# 3-3.net
KiCad netlist of a schematic drawn in Altium Designer
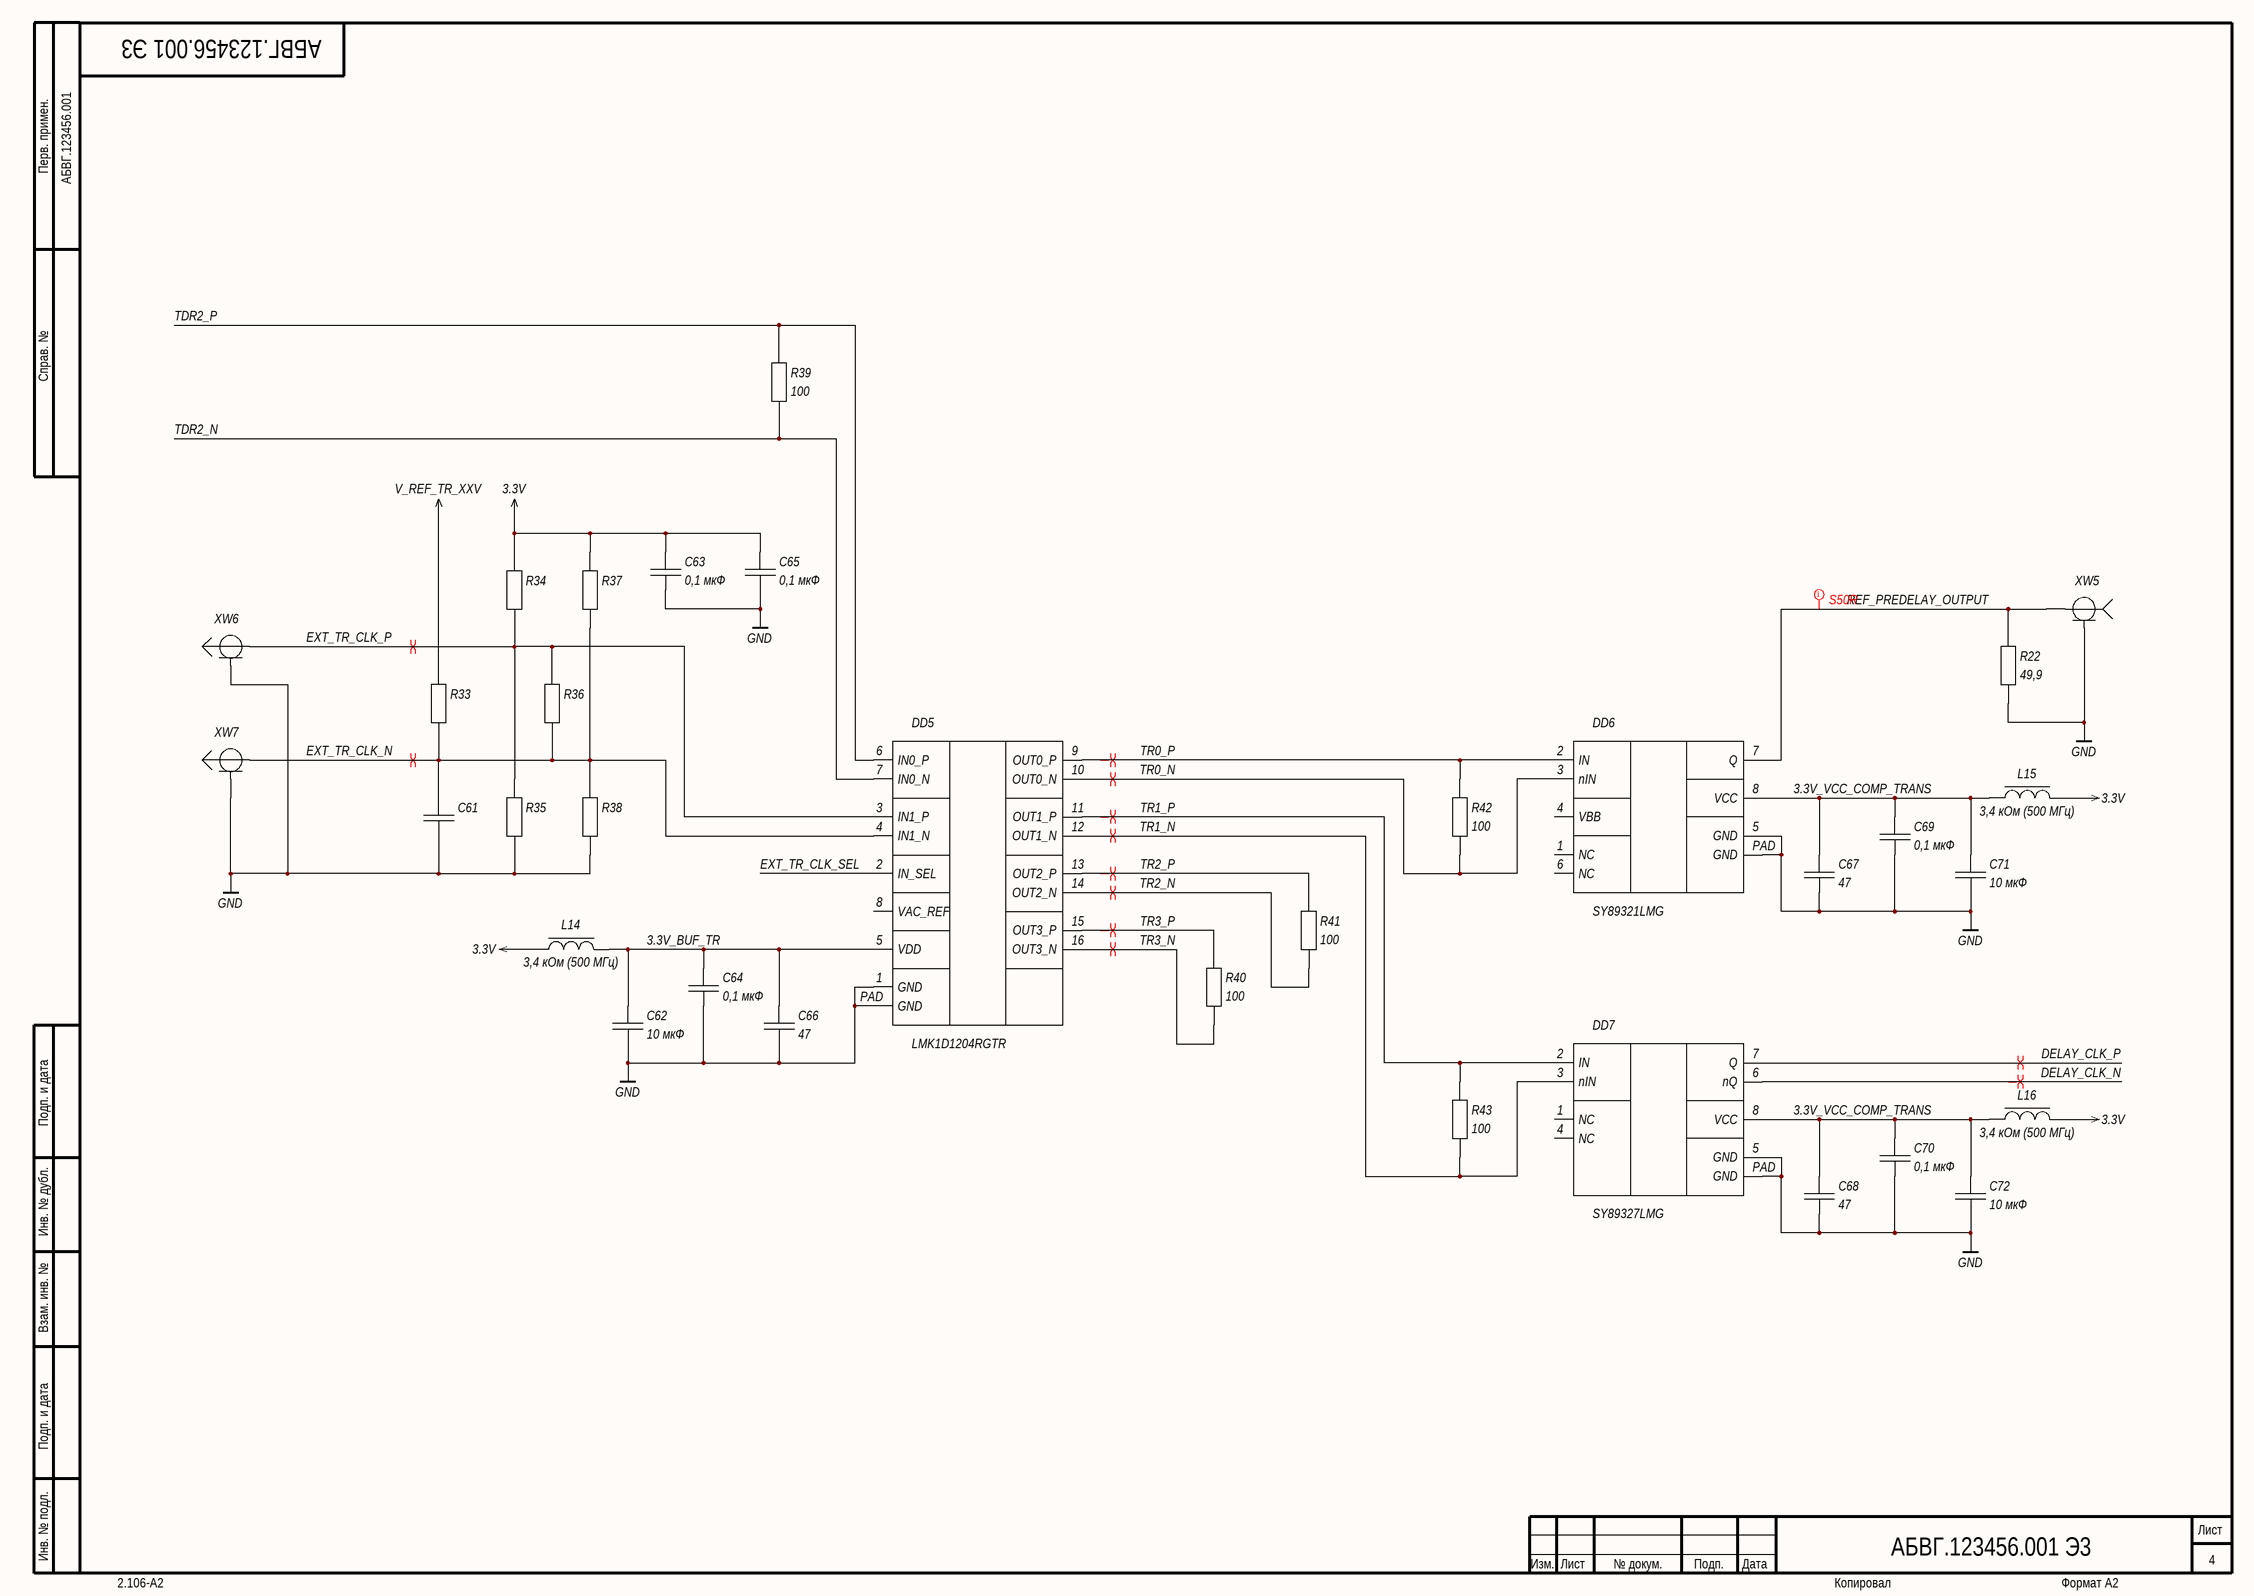
[diagram p0: Э3-3 Внешний триггер.SchDoc]

(export (version "E")
  (design (tool "Eeschema 10.0.6"))
  (components
    (comp (ref "C61")
      (value "~")
      (footprint "C0402-B-0.5mm")
      (fields (field (name "PARTNUMBER") "GRM155R71H104KE14D"))
      (libsource (lib "Capacitors") (part "Non Polar Ver."))
    )
    (comp (ref "C62")
      (value "10 мкФ")
      (footprint "C0603-B-0.8mm")
      (description "0603 X5R 10 мкФ ±20 % 25 В")
      (fields (field (name "PARTNUMBER") "GRM188R61E106MA73"))
      (libsource (lib "Capacitors") (part "Non Polar Ver."))
    )
    (comp (ref "C63")
      (value "0,1 мкФ")
      (footprint "C0402-B-0.5mm")
      (description "0402 X7R 0,1 мкФ ±10 % 50 В")
      (fields (field (name "PARTNUMBER") "GRM155R71H104KE14D"))
      (libsource (lib "Capacitors") (part "Non Polar Ver."))
    )
    (comp (ref "C64")
      (value "0,1 мкФ")
      (footprint "C0402-B-0.5mm")
      (description "0402 X7R 0,1 мкФ ±10 % 50 В")
      (fields (field (name "PARTNUMBER") "GRM155R71H104KE14D"))
      (libsource (lib "Capacitors") (part "Non Polar Ver."))
    )
    (comp (ref "C65")
      (value "0,1 мкФ")
      (footprint "C0402-B-0.5mm")
      (description "0402 X7R 0,1 мкФ ±10 % 50 В")
      (fields (field (name "PARTNUMBER") "GRM155R71H104KE14D"))
      (libsource (lib "Capacitors") (part "Non Polar Ver."))
    )
    (comp (ref "C66")
      (value "47")
      (footprint "C0402-B-0.5mm")
      (description "0402 NP0 47 пФ ±5 % 50 В")
      (fields (field (name "PARTNUMBER") "GCM1555C1H470JA16"))
      (libsource (lib "Capacitors") (part "Non Polar Ver."))
    )
    (comp (ref "C67")
      (value "47")
      (footprint "C0402-B-0.5mm")
      (description "0402 NP0 47 пФ ±5 % 50 В")
      (fields (field (name "PARTNUMBER") "GCM1555C1H470JA16"))
      (libsource (lib "Capacitors") (part "Non Polar Ver."))
    )
    (comp (ref "C68")
      (value "47")
      (footprint "C0402-B-0.5mm")
      (description "0402 NP0 47 пФ ±5 % 50 В")
      (fields (field (name "PARTNUMBER") "GCM1555C1H470JA16"))
      (libsource (lib "Capacitors") (part "Non Polar Ver."))
    )
    (comp (ref "C69")
      (value "0,1 мкФ")
      (footprint "C0402-B-0.5mm")
      (description "0402 X7R 0,1 мкФ ±10 % 50 В")
      (fields (field (name "PARTNUMBER") "GRM155R71H104KE14D"))
      (libsource (lib "Capacitors") (part "Non Polar Ver."))
    )
    (comp (ref "C70")
      (value "0,1 мкФ")
      (footprint "C0402-B-0.5mm")
      (description "0402 X7R 0,1 мкФ ±10 % 50 В")
      (fields (field (name "PARTNUMBER") "GRM155R71H104KE14D"))
      (libsource (lib "Capacitors") (part "Non Polar Ver."))
    )
    (comp (ref "C71")
      (value "10 мкФ")
      (footprint "C0603-B-0.8mm")
      (description "0603 X5R 10 мкФ ±20 % 25 В")
      (fields (field (name "PARTNUMBER") "GRM188R61E106MA73"))
      (libsource (lib "Capacitors") (part "Non Polar Ver."))
    )
    (comp (ref "C72")
      (value "10 мкФ")
      (footprint "C0603-B-0.8mm")
      (description "0603 X5R 10 мкФ ±20 % 25 В")
      (fields (field (name "PARTNUMBER") "GRM188R61E106MA73"))
      (libsource (lib "Capacitors") (part "Non Polar Ver."))
    )
    (comp (ref "DD5")
      (value "LMK1D1204RGTR")
      (footprint "16-QFN-3-H1-EP1.7")
      (description "Low Additive Jitter LVDS Buffer")
      (fields (field (name "MANUFACTURER") "Texas Instruments, Inc."))
      (libsource (lib "Digital") (part "LMK1D1204"))
    )
    (comp (ref "DD6")
      (value "SY89321LMG")
      (footprint "8-MLF")
      (description "3.3V DIFFERENTIAL LVPECL/CML/LVDS-to-LVTTL TRANSLATOR")
      (fields (field (name "MANUFACTURER") "Microchip Technology"))
      (libsource (lib "Digital") (part "SY89321L"))
    )
    (comp (ref "DD7")
      (value "SY89327LMG")
      (footprint "8-MLF")
      (description "3.3V 2.5Gbps ANY INPUT-to-LVPECL DIFFERENTIAL TRANSLATOR")
      (fields (field (name "MANUFACTURER") "Microchip Technology"))
      (libsource (lib "Digital") (part "SY89327L"))
    )
    (comp (ref "L14")
      (value "3,4 кОм (500 МГц)")
      (footprint "L0402-B-0.5mm")
      (fields (field (name "PARTNUMBER") "BLM15HD182BH1"))
      (libsource (lib "Inductors") (part "Inductor MC Hor."))
    )
    (comp (ref "L15")
      (value "3,4 кОм (500 МГц)")
      (footprint "L0402-B-0.5mm")
      (fields (field (name "PARTNUMBER") "BLM15HD182BH1"))
      (libsource (lib "Inductors") (part "Inductor MC Hor."))
    )
    (comp (ref "L16")
      (value "3,4 кОм (500 МГц)")
      (footprint "L0402-B-0.5mm")
      (fields (field (name "PARTNUMBER") "BLM15HD182BH1"))
      (libsource (lib "Inductors") (part "Inductor MC Hor."))
    )
    (comp (ref "R22")
      (value "49,9")
      (footprint "CR0402-B-0.35mm")
      (description "0402 49,9 Ом ±1 %")
      (libsource (lib "Resistors") (part "Resistor Ver."))
    )
    (comp (ref "R33")
      (value "~")
      (footprint "CR0402-B-0.35mm")
      (libsource (lib "Resistors") (part "Resistor Ver."))
    )
    (comp (ref "R34")
      (value "~")
      (footprint "CR0402-B-0.35mm")
      (libsource (lib "Resistors") (part "Resistor Ver."))
    )
    (comp (ref "R35")
      (value "~")
      (footprint "CR0402-B-0.35mm")
      (libsource (lib "Resistors") (part "Resistor Ver."))
    )
    (comp (ref "R36")
      (value "~")
      (footprint "CR0402-B-0.35mm")
      (libsource (lib "Resistors") (part "Resistor Ver."))
    )
    (comp (ref "R37")
      (value "~")
      (footprint "CR0402-B-0.35mm")
      (libsource (lib "Resistors") (part "Resistor Ver."))
    )
    (comp (ref "R38")
      (value "~")
      (footprint "CR0402-B-0.35mm")
      (libsource (lib "Resistors") (part "Resistor Ver."))
    )
    (comp (ref "R39")
      (value "100")
      (footprint "CR0402-B-0.35mm")
      (description "0402 100 Ом ±1 %")
      (libsource (lib "Resistors") (part "Resistor Ver."))
    )
    (comp (ref "R40")
      (value "100")
      (footprint "CR0402-B-0.35mm")
      (description "0402 100 Ом ±1 %")
      (libsource (lib "Resistors") (part "Resistor Ver."))
    )
    (comp (ref "R41")
      (value "100")
      (footprint "CR0402-B-0.35mm")
      (description "0402 100 Ом ±1 %")
      (libsource (lib "Resistors") (part "Resistor Ver."))
    )
    (comp (ref "R42")
      (value "100")
      (footprint "CR0402-B-0.35mm")
      (description "0402 100 Ом ±1 %")
      (libsource (lib "Resistors") (part "Resistor Ver."))
    )
    (comp (ref "R43")
      (value "100")
      (footprint "CR0402-B-0.35mm")
      (description "0402 100 Ом ±1 %")
      (libsource (lib "Resistors") (part "Resistor Ver."))
    )
    (comp (ref "XW5")
      (value "XW(S)")
      (footprint "SMA-J-P-H-ST-EM1")
      (libsource (lib "Connectors") (part "XW(S)"))
    )
    (comp (ref "XW6")
      (value "XW(P)")
      (footprint "U.FL STR PLG")
      (libsource (lib "Connectors") (part "XW(P)"))
    )
    (comp (ref "XW7")
      (value "XW(P)")
      (footprint "U.FL STR PLG")
      (libsource (lib "Connectors") (part "XW(P)"))
    )
  )
  (nets
    (net (code "1") (name "/3.3V_BUF_TR") (class "Default")
      (node (ref "C62") (pin "1") (pinfunction "1_1") (pintype "passive"))
      (node (ref "C64") (pin "1") (pinfunction "1_1") (pintype "passive"))
      (node (ref "C66") (pin "1") (pinfunction "1_1") (pintype "passive"))
      (node (ref "DD5") (pin "5") (pinfunction "VDD_5") (pintype "passive"))
      (node (ref "L14") (pin "2") (pinfunction "2_2") (pintype "passive"))
    )
    (net (code "2") (name "/3.3V_VCC_COMP_TRANS") (class "Default")
      (node (ref "C67") (pin "1") (pinfunction "1_1") (pintype "passive"))
      (node (ref "C68") (pin "1") (pinfunction "1_1") (pintype "passive"))
      (node (ref "C69") (pin "1") (pinfunction "1_1") (pintype "passive"))
      (node (ref "C70") (pin "1") (pinfunction "1_1") (pintype "passive"))
      (node (ref "C71") (pin "1") (pinfunction "1_1") (pintype "passive"))
      (node (ref "C72") (pin "1") (pinfunction "1_1") (pintype "passive"))
      (node (ref "DD6") (pin "8") (pinfunction "VCC_8") (pintype "passive"))
      (node (ref "DD7") (pin "8") (pinfunction "VCC_8") (pintype "passive"))
      (node (ref "L15") (pin "1") (pinfunction "1_1") (pintype "passive"))
      (node (ref "L16") (pin "1") (pinfunction "1_1") (pintype "passive"))
    )
    (net (code "3") (name "/DELAY_CLK_N") (class "Default")
      (node (ref "DD7") (pin "6") (pinfunction "nQ_6") (pintype "passive"))
    )
    (net (code "4") (name "/DELAY_CLK_P") (class "Default")
      (node (ref "DD7") (pin "7") (pinfunction "Q_7") (pintype "passive"))
    )
    (net (code "5") (name "/EXT_TR_CLK_N") (class "Default")
      (node (ref "C61") (pin "1") (pinfunction "1_1") (pintype "passive"))
      (node (ref "DD5") (pin "4") (pinfunction "IN1_N_4") (pintype "passive"))
      (node (ref "R33") (pin "2") (pinfunction "2_2") (pintype "passive"))
      (node (ref "R36") (pin "2") (pinfunction "2_2") (pintype "passive"))
      (node (ref "R37") (pin "2") (pinfunction "2_2") (pintype "passive"))
      (node (ref "R38") (pin "1") (pinfunction "1_1") (pintype "passive"))
      (node (ref "XW7") (pin "1") (pinfunction "1_1") (pintype "passive"))
    )
    (net (code "6") (name "/EXT_TR_CLK_P") (class "Default")
      (node (ref "DD5") (pin "3") (pinfunction "IN1_P_3") (pintype "passive"))
      (node (ref "R34") (pin "2") (pinfunction "2_2") (pintype "passive"))
      (node (ref "R35") (pin "1") (pinfunction "1_1") (pintype "passive"))
      (node (ref "R36") (pin "1") (pinfunction "1_1") (pintype "passive"))
      (node (ref "XW6") (pin "1") (pinfunction "1_1") (pintype "passive"))
    )
    (net (code "7") (name "/EXT_TR_CLK_SEL") (class "Default")
      (node (ref "DD5") (pin "2") (pinfunction "IN_SEL_2") (pintype "passive"))
    )
    (net (code "8") (name "/REF_PREDELAY_OUTPUT") (class "Default")
      (node (ref "DD6") (pin "7") (pinfunction "Q_7") (pintype "passive"))
      (node (ref "R22") (pin "1") (pinfunction "1_1") (pintype "passive"))
      (node (ref "XW5") (pin "1") (pinfunction "1_1") (pintype "passive"))
    )
    (net (code "9") (name "/TDR2_N") (class "Default")
      (node (ref "DD5") (pin "7") (pinfunction "IN0_N_7") (pintype "passive"))
      (node (ref "R39") (pin "2") (pinfunction "2_2") (pintype "passive"))
    )
    (net (code "10") (name "/TDR2_P") (class "Default")
      (node (ref "DD5") (pin "6") (pinfunction "IN0_P_6") (pintype "passive"))
      (node (ref "R39") (pin "1") (pinfunction "1_1") (pintype "passive"))
    )
    (net (code "11") (name "/TR0_N") (class "Default")
      (node (ref "DD5") (pin "10") (pinfunction "OUT0_N_10") (pintype "passive"))
      (node (ref "DD6") (pin "3") (pinfunction "nIN_3") (pintype "passive"))
      (node (ref "R42") (pin "2") (pinfunction "2_2") (pintype "passive"))
    )
    (net (code "12") (name "/TR0_P") (class "Default")
      (node (ref "DD5") (pin "9") (pinfunction "OUT0_P_9") (pintype "passive"))
      (node (ref "DD6") (pin "2") (pinfunction "IN_2") (pintype "passive"))
      (node (ref "R42") (pin "1") (pinfunction "1_1") (pintype "passive"))
    )
    (net (code "13") (name "/TR1_N") (class "Default")
      (node (ref "DD5") (pin "12") (pinfunction "OUT1_N_12") (pintype "passive"))
      (node (ref "DD7") (pin "3") (pinfunction "nIN_3") (pintype "passive"))
      (node (ref "R43") (pin "2") (pinfunction "2_2") (pintype "passive"))
    )
    (net (code "14") (name "/TR1_P") (class "Default")
      (node (ref "DD5") (pin "11") (pinfunction "OUT1_P_11") (pintype "passive"))
      (node (ref "DD7") (pin "2") (pinfunction "IN_2") (pintype "passive"))
      (node (ref "R43") (pin "1") (pinfunction "1_1") (pintype "passive"))
    )
    (net (code "15") (name "/TR2_N") (class "Default")
      (node (ref "DD5") (pin "14") (pinfunction "OUT2_N_14") (pintype "passive"))
      (node (ref "R41") (pin "2") (pinfunction "2_2") (pintype "passive"))
    )
    (net (code "16") (name "/TR2_P") (class "Default")
      (node (ref "DD5") (pin "13") (pinfunction "OUT2_P_13") (pintype "passive"))
      (node (ref "R41") (pin "1") (pinfunction "1_1") (pintype "passive"))
    )
    (net (code "17") (name "/TR3_N") (class "Default")
      (node (ref "DD5") (pin "16") (pinfunction "OUT3_N_16") (pintype "passive"))
      (node (ref "R40") (pin "2") (pinfunction "2_2") (pintype "passive"))
    )
    (net (code "18") (name "/TR3_P") (class "Default")
      (node (ref "DD5") (pin "15") (pinfunction "OUT3_P_15") (pintype "passive"))
      (node (ref "R40") (pin "1") (pinfunction "1_1") (pintype "passive"))
    )
    (net (code "19") (name "3.3V") (class "Default")
      (node (ref "C63") (pin "1") (pinfunction "1_1") (pintype "passive"))
      (node (ref "C65") (pin "1") (pinfunction "1_1") (pintype "passive"))
      (node (ref "L14") (pin "1") (pinfunction "1_1") (pintype "passive"))
      (node (ref "L15") (pin "2") (pinfunction "2_2") (pintype "passive"))
      (node (ref "L16") (pin "2") (pinfunction "2_2") (pintype "passive"))
      (node (ref "R34") (pin "1") (pinfunction "1_1") (pintype "passive"))
      (node (ref "R37") (pin "1") (pinfunction "1_1") (pintype "passive"))
    )
    (net (code "20") (name "GND") (class "Default")
      (node (ref "C61") (pin "2") (pinfunction "2_2") (pintype "passive"))
      (node (ref "C62") (pin "2") (pinfunction "2_2") (pintype "passive"))
      (node (ref "C63") (pin "2") (pinfunction "2_2") (pintype "passive"))
      (node (ref "C64") (pin "2") (pinfunction "2_2") (pintype "passive"))
      (node (ref "C65") (pin "2") (pinfunction "2_2") (pintype "passive"))
      (node (ref "C66") (pin "2") (pinfunction "2_2") (pintype "passive"))
      (node (ref "C67") (pin "2") (pinfunction "2_2") (pintype "passive"))
      (node (ref "C68") (pin "2") (pinfunction "2_2") (pintype "passive"))
      (node (ref "C69") (pin "2") (pinfunction "2_2") (pintype "passive"))
      (node (ref "C70") (pin "2") (pinfunction "2_2") (pintype "passive"))
      (node (ref "C71") (pin "2") (pinfunction "2_2") (pintype "passive"))
      (node (ref "C72") (pin "2") (pinfunction "2_2") (pintype "passive"))
      (node (ref "DD5") (pin "1") (pinfunction "GND_1") (pintype "passive"))
      (node (ref "DD5") (pin "PAD") (pinfunction "GND_PAD") (pintype "passive"))
      (node (ref "DD6") (pin "5") (pinfunction "GND_5") (pintype "passive"))
      (node (ref "DD6") (pin "PAD") (pinfunction "GND_PAD") (pintype "passive"))
      (node (ref "DD7") (pin "5") (pinfunction "GND_5") (pintype "passive"))
      (node (ref "DD7") (pin "PAD") (pinfunction "GND_PAD") (pintype "passive"))
      (node (ref "R22") (pin "2") (pinfunction "2_2") (pintype "passive"))
      (node (ref "R35") (pin "2") (pinfunction "2_2") (pintype "passive"))
      (node (ref "R38") (pin "2") (pinfunction "2_2") (pintype "passive"))
      (node (ref "XW5") (pin "2") (pinfunction "2_2") (pintype "passive"))
      (node (ref "XW6") (pin "2") (pinfunction "2_2") (pintype "passive"))
      (node (ref "XW7") (pin "2") (pinfunction "2_2") (pintype "passive"))
    )
    (net (code "21") (name "V_REF_TR_XXV") (class "Default")
      (node (ref "R33") (pin "1") (pinfunction "1_1") (pintype "passive"))
    )
    (net (code "22") (name "unconnected-(DD5-VAC_REF-Pad8)") (class "Default")
      (node (ref "DD5") (pin "8") (pinfunction "VAC_REF_8") (pintype "passive"))
    )
    (net (code "23") (name "unconnected-(DD6-NC-Pad1)") (class "Default")
      (node (ref "DD6") (pin "1") (pinfunction "NC_1") (pintype "passive"))
    )
    (net (code "24") (name "unconnected-(DD6-NC-Pad6)") (class "Default")
      (node (ref "DD6") (pin "6") (pinfunction "NC_6") (pintype "passive"))
    )
    (net (code "25") (name "unconnected-(DD6-VBB-Pad4)") (class "Default")
      (node (ref "DD6") (pin "4") (pinfunction "VBB_4") (pintype "passive"))
    )
    (net (code "26") (name "unconnected-(DD7-NC-Pad1)") (class "Default")
      (node (ref "DD7") (pin "1") (pinfunction "NC_1") (pintype "passive"))
    )
    (net (code "27") (name "unconnected-(DD7-NC-Pad4)") (class "Default")
      (node (ref "DD7") (pin "4") (pinfunction "NC_4") (pintype "passive"))
    )
  )
)
